# Sheet1.net
KiCad netlist of a schematic drawn in Altium Designer
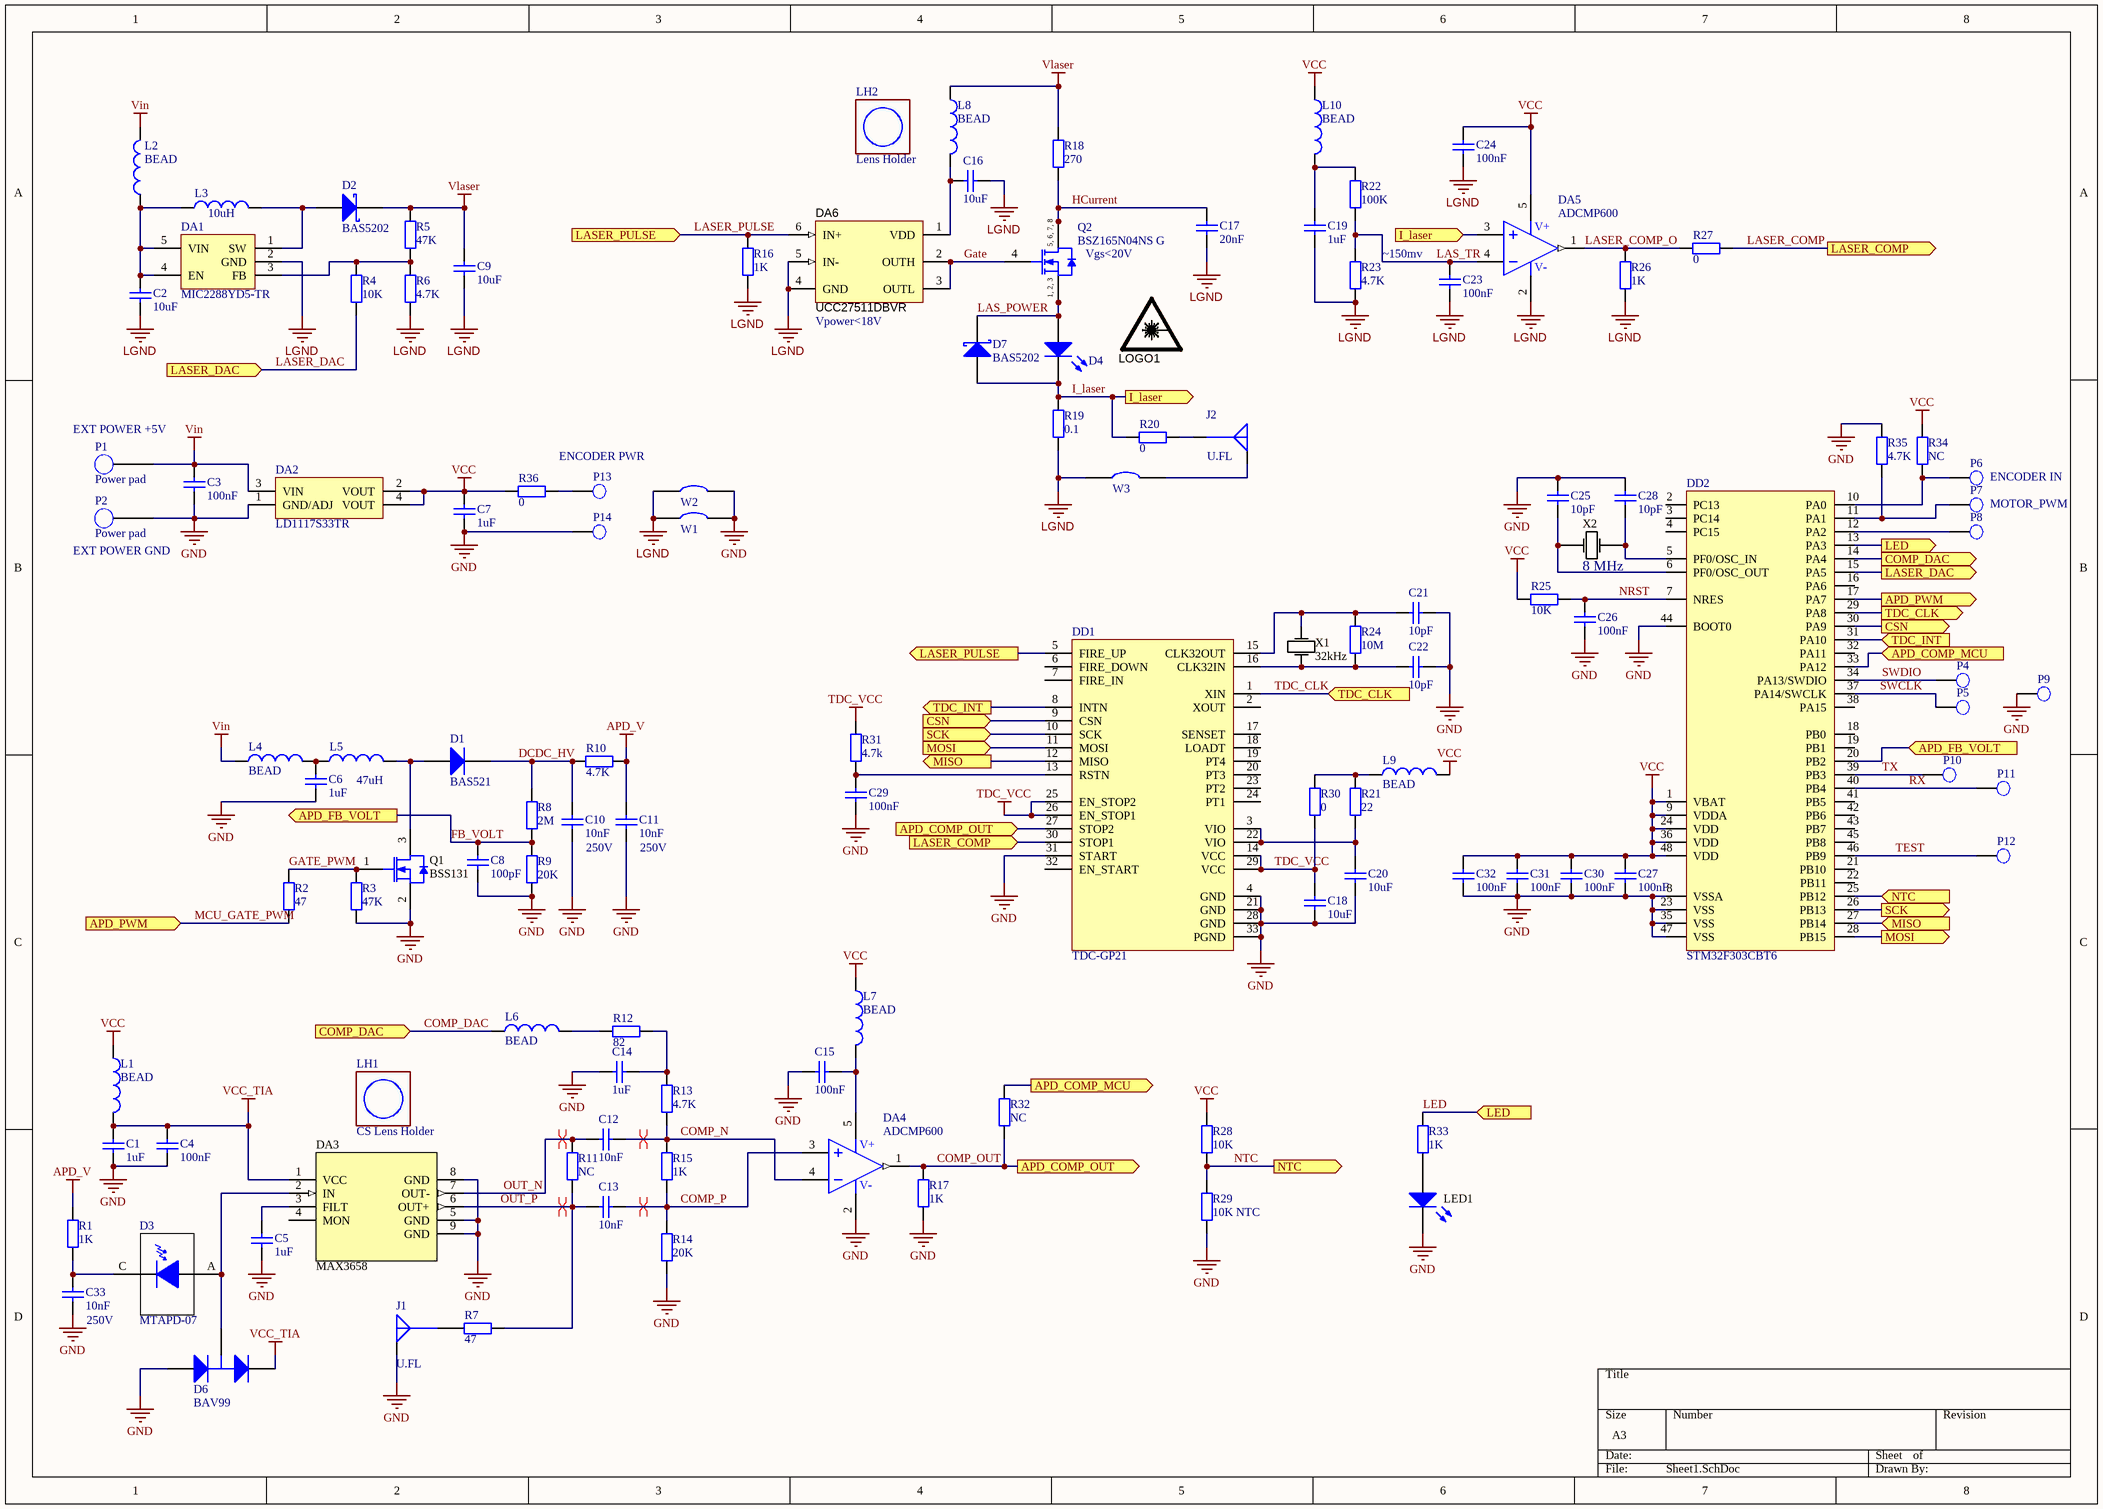
[diagram p0: Sheet1.SchDoc]

(export (version "E")
  (design (tool "Eeschema 10.0.6"))
  (components
    (comp (ref "C1")
      (value "1uF")
      (footprint "CAPC2012X135N")
      (description "Chip capacitor")
      (fields (field (name "VOLTAGE") "25V"))
      (libsource (lib "MyLibSch") (part "CC0805"))
    )
    (comp (ref "C2")
      (value "10uF")
      (footprint "CAPC1608X90N")
      (description "Chip capacitor")
      (fields (field (name "VOLTAGE") "25V"))
      (libsource (lib "MyLibSch") (part "CC0805"))
    )
    (comp (ref "C3")
      (value "100nF")
      (footprint "CAPC1608X90N")
      (description "Chip capacitor")
      (fields (field (name "VOLTAGE") "25V"))
      (libsource (lib "MyLibSch") (part "CC0805"))
    )
    (comp (ref "C4")
      (value "100nF")
      (footprint "CAPC1608X90N")
      (description "Chip capacitor")
      (fields (field (name "VOLTAGE") "25V"))
      (libsource (lib "MyLibSch") (part "CC0805"))
    )
    (comp (ref "C5")
      (value "1uF")
      (footprint "CAPC1608X90N")
      (description "Chip capacitor")
      (fields (field (name "VOLTAGE") "25V"))
      (libsource (lib "MyLibSch") (part "CC0805"))
    )
    (comp (ref "C6")
      (value "1uF")
      (footprint "CAPC2012X135N")
      (description "Chip capacitor")
      (fields (field (name "VOLTAGE") "25V"))
      (libsource (lib "MyLibSch") (part "CC0805"))
    )
    (comp (ref "C7")
      (value "1uF")
      (footprint "CAPC2012X135N")
      (description "Chip capacitor")
      (fields (field (name "VOLTAGE") "25V"))
      (libsource (lib "MyLibSch") (part "CC0805"))
    )
    (comp (ref "C8")
      (value "100pF")
      (footprint "CAPC1608X90N")
      (description "Chip capacitor")
      (fields (field (name "VOLTAGE") "25V"))
      (libsource (lib "MyLibSch") (part "CC0805"))
    )
    (comp (ref "C9")
      (value "10uF")
      (footprint "CAPC1608X90N")
      (description "Chip capacitor")
      (fields (field (name "VOLTAGE") "50V"))
      (libsource (lib "MyLibSch") (part "CC0805"))
    )
    (comp (ref "C10")
      (value "10nF")
      (footprint "CAPC2012X135N")
      (description "Chip capacitor")
      (fields (field (name "VOLTAGE") "250V"))
      (libsource (lib "MyLibSch") (part "CC0805"))
    )
    (comp (ref "C11")
      (value "10nF")
      (footprint "CAPC2012X135N")
      (description "Chip capacitor")
      (fields (field (name "VOLTAGE") "250V"))
      (libsource (lib "MyLibSch") (part "CC0805"))
    )
    (comp (ref "C12")
      (value "10nF")
      (footprint "CAPC1608X90N")
      (description "Chip capacitor")
      (fields (field (name "VOLTAGE") "25V"))
      (libsource (lib "MyLibSch") (part "CC0805"))
    )
    (comp (ref "C13")
      (value "10nF")
      (footprint "CAPC1608X90N")
      (description "Chip capacitor")
      (fields (field (name "VOLTAGE") "25V"))
      (libsource (lib "MyLibSch") (part "CC0805"))
    )
    (comp (ref "C14")
      (value "1uF")
      (footprint "CAPC2012X135N")
      (description "Chip capacitor")
      (fields (field (name "VOLTAGE") "25V"))
      (libsource (lib "MyLibSch") (part "CC0805"))
    )
    (comp (ref "C15")
      (value "100nF")
      (footprint "CAPC1608X90N")
      (description "Chip capacitor")
      (fields (field (name "VOLTAGE") "25V"))
      (libsource (lib "MyLibSch") (part "CC0805"))
    )
    (comp (ref "C16")
      (value "10uF")
      (footprint "CAPC1608X90N")
      (description "Chip capacitor")
      (fields (field (name "VOLTAGE") "25V"))
      (libsource (lib "MyLibSch") (part "CC0805"))
    )
    (comp (ref "C17")
      (value "20nF")
      (footprint "CAPC1608X90N")
      (description "Chip capacitor")
      (fields (field (name "VOLTAGE") "50V"))
      (libsource (lib "MyLibSch") (part "CC0805"))
    )
    (comp (ref "C18")
      (value "10uF")
      (footprint "CAPC1608X90N")
      (description "Chip capacitor")
      (fields (field (name "VOLTAGE") "25V"))
      (libsource (lib "MyLibSch") (part "CC0805"))
    )
    (comp (ref "C19")
      (value "1uF")
      (footprint "CAPC2012X135N")
      (description "Chip capacitor")
      (fields (field (name "VOLTAGE") "25V"))
      (libsource (lib "MyLibSch") (part "CC0805"))
    )
    (comp (ref "C20")
      (value "10uF")
      (footprint "CAPC1608X90N")
      (description "Chip capacitor")
      (fields (field (name "VOLTAGE") "25V"))
      (libsource (lib "MyLibSch") (part "CC0805"))
    )
    (comp (ref "C21")
      (value "10pF")
      (footprint "CAPC1608X90N")
      (description "Chip capacitor")
      (fields (field (name "VOLTAGE") "25V"))
      (libsource (lib "MyLibSch") (part "CC0805"))
    )
    (comp (ref "C22")
      (value "10pF")
      (footprint "CAPC1608X90N")
      (description "Chip capacitor")
      (fields (field (name "VOLTAGE") "25V"))
      (libsource (lib "MyLibSch") (part "CC0805"))
    )
    (comp (ref "C23")
      (value "100nF")
      (footprint "CAPC1608X90N")
      (description "Chip capacitor")
      (fields (field (name "VOLTAGE") "25V"))
      (libsource (lib "MyLibSch") (part "CC0805"))
    )
    (comp (ref "C24")
      (value "100nF")
      (footprint "CAPC1608X90N")
      (description "Chip capacitor")
      (fields (field (name "VOLTAGE") "25V"))
      (libsource (lib "MyLibSch") (part "CC0805"))
    )
    (comp (ref "C25")
      (value "10pF")
      (footprint "CAPC1608X90N")
      (description "Chip capacitor")
      (fields (field (name "VOLTAGE") "25V"))
      (libsource (lib "MyLibSch") (part "CC0805"))
    )
    (comp (ref "C26")
      (value "100nF")
      (footprint "CAPC1608X90N")
      (description "Chip capacitor")
      (fields (field (name "VOLTAGE") "25V"))
      (libsource (lib "MyLibSch") (part "CC0805"))
    )
    (comp (ref "C27")
      (value "100nF")
      (footprint "CAPC1608X90N")
      (description "Chip capacitor")
      (fields (field (name "VOLTAGE") "25V"))
      (libsource (lib "MyLibSch") (part "CC0805"))
    )
    (comp (ref "C28")
      (value "10pF")
      (footprint "CAPC1608X90N")
      (description "Chip capacitor")
      (fields (field (name "VOLTAGE") "25V"))
      (libsource (lib "MyLibSch") (part "CC0805"))
    )
    (comp (ref "C29")
      (value "100nF")
      (footprint "CAPC1608X90N")
      (description "Chip capacitor")
      (fields (field (name "VOLTAGE") "25V"))
      (libsource (lib "MyLibSch") (part "CC0805"))
    )
    (comp (ref "C30")
      (value "100nF")
      (footprint "CAPC1608X90N")
      (description "Chip capacitor")
      (fields (field (name "VOLTAGE") "25V"))
      (libsource (lib "MyLibSch") (part "CC0805"))
    )
    (comp (ref "C31")
      (value "100nF")
      (footprint "CAPC1608X90N")
      (description "Chip capacitor")
      (fields (field (name "VOLTAGE") "25V"))
      (libsource (lib "MyLibSch") (part "CC0805"))
    )
    (comp (ref "C32")
      (value "100nF")
      (footprint "CAPC1608X90N")
      (description "Chip capacitor")
      (fields (field (name "VOLTAGE") "25V"))
      (libsource (lib "MyLibSch") (part "CC0805"))
    )
    (comp (ref "C33")
      (value "10nF")
      (footprint "CAPC2012X135N")
      (description "Chip capacitor")
      (fields (field (name "VOLTAGE") "250V"))
      (libsource (lib "MyLibSch") (part "CC0805"))
    )
    (comp (ref "D1") (value "BAS521") (footprint "SOD523F") (libsource (lib "MyLibSch") (part "DIODE 2 pin")))
    (comp (ref "D2")
      (value "BAS5202")
      (footprint "SOD523F")
      (description "Schottky Diode")
      (fields (field (name "PUBLISHER") "Altium Limited"))
      (libsource (lib "Miscellaneous Devices") (part "D Schottky"))
    )
    (comp (ref "D3")
      (value "MTAPD-07")
      (footprint "LCC3")
      (description "APD photodiode")
      (libsource (lib "lcd_lib") (part "MTAPD-07"))
    )
    (comp (ref "D4")
      (value "Laser SPL PL90_3")
      (footprint "SPL_PL90")
      (description "TO-18 Laser")
      (libsource (lib "lcd_lib") (part "TO-18 Laser"))
    )
    (comp (ref "D6")
      (value "BAV99")
      (footprint "SOT-23")
      (description "Silicon Switching Diode Array for High-Speed Switching")
      (fields (field (name "PUBLISHER") "Altium Limited"))
      (libsource (lib "Infineon Discrete Diode") (part "BAV99"))
    )
    (comp (ref "D7")
      (value "BAS5202")
      (footprint "SOD523F")
      (description "Schottky Diode")
      (fields (field (name "PUBLISHER") "Altium Limited"))
      (libsource (lib "Miscellaneous Devices") (part "D Schottky"))
    )
    (comp (ref "DA1")
      (value "MIC2288YD5-TR")
      (footprint "SOT23-5")
      (description "Step Up")
      (libsource (lib "lcd_lib") (part "MIC2288"))
    )
    (comp (ref "DA2")
      (value "LD1117S33TR")
      (footprint "SOT223")
      (description "LOW DROP FIXED AND ADJUSTABLE  POSITIVE VOLTAGE REGULATORS")
      (libsource (lib "MyLibSch") (part "LD1117S"))
    )
    (comp (ref "DA3")
      (value "MAX3658")
      (footprint "TDFN-8_0.65")
      (description "Transimpedance Amplifier")
      (fields (field (name "PART NUMBER") "AD7278"))
      (libsource (lib "lcd_lib") (part "MAX3658"))
    )
    (comp (ref "DA4")
      (value "ADCMP600")
      (footprint "SOT23-5")
      (description "Fast comparator")
      (libsource (lib "lcd_lib") (part "ADCMP600"))
    )
    (comp (ref "DA5")
      (value "ADCMP600")
      (footprint "SOT23-5")
      (description "Fast comparator")
      (libsource (lib "lcd_lib") (part "ADCMP600"))
    )
    (comp (ref "DA6")
      (value "UCC27511DBVR")
      (footprint "Miscellaneous Devices:SOT23-6_M")
      (description "Single-Channel High-Speed Low-Side Gate Driver (with 4-A Peak Source and 8-A Peak Sink), DBV0006A")
      (fields
        (field (name "ALTERNATE PARTNUMBER") "UCC27511DBVT")
        (field (name "MANUFACTURER") "Texas Instruments")
        (field (name "SYMBOLCREATOR") "a0411947")
        (field (name "PUBLISHER") "Texas Instruments")
      )
      (libsource (lib "TI_Pre_Release") (part "UCC27511DBVR"))
    )
    (comp (ref "DD1")
      (value "TDC-GP21")
      (footprint "QFN32 5x5mm")
      (description "TDC")
      (libsource (lib "lcd_lib") (part "TDC_GP21"))
    )
    (comp (ref "DD2")
      (value "STM32F303CBT6")
      (footprint "LQFP-48_N")
      (description "Microcontroller")
      (libsource (lib "lcd_lib") (part "STM32F3_LQFP48"))
    )
    (comp (ref "J1")
      (value "U.FL")
      (footprint "TE C-1909763")
      (description "U.FL Connector")
      (libsource (lib "RF Connector") (part "RF Connector - SMA"))
    )
    (comp (ref "J2")
      (value "U.FL")
      (footprint "TE C-1909763")
      (description "U.FL Connector")
      (libsource (lib "RF Connector") (part "RF Connector - SMA"))
    )
    (comp (ref "L1")
      (value "BEAD")
      (footprint "INDC1608N")
      (description "Ferrit Bead")
      (libsource (lib "MyLibSch") (part "BEAD"))
    )
    (comp (ref "L2")
      (value "BEAD")
      (footprint "INDC1608N")
      (description "Ferrit Bead")
      (libsource (lib "MyLibSch") (part "BEAD"))
    )
    (comp (ref "L3")
      (value "10uH")
      (footprint "MyLibPcb:V0805HD")
      (description "Inductor")
      (fields (field (name "PUBLISHER") "Altium Limited"))
      (libsource (lib "Miscellaneous Devices") (part "Inductor"))
    )
    (comp (ref "L4")
      (value "BEAD")
      (footprint "INDC1608N")
      (description "Ferrit Bead")
      (libsource (lib "MyLibSch") (part "BEAD"))
    )
    (comp (ref "L5")
      (value "47uH")
      (footprint "INDC3216")
      (description "Inductor")
      (fields (field (name "PUBLISHER") "Altium Limited"))
      (libsource (lib "Miscellaneous Devices") (part "Inductor"))
    )
    (comp (ref "L6")
      (value "BEAD")
      (footprint "INDC1608N")
      (description "Ferrit Bead")
      (libsource (lib "MyLibSch") (part "BEAD"))
    )
    (comp (ref "L7")
      (value "BEAD")
      (footprint "INDC1608N")
      (description "Ferrit Bead")
      (libsource (lib "MyLibSch") (part "BEAD"))
    )
    (comp (ref "L8")
      (value "BEAD")
      (footprint "INDC1608N")
      (description "Ferrit Bead")
      (libsource (lib "MyLibSch") (part "BEAD"))
    )
    (comp (ref "L9")
      (value "BEAD")
      (footprint "INDC1608N")
      (description "Ferrit Bead")
      (libsource (lib "MyLibSch") (part "BEAD"))
    )
    (comp (ref "L10")
      (value "BEAD")
      (footprint "INDC1608N")
      (description "Ferrit Bead")
      (libsource (lib "MyLibSch") (part "BEAD"))
    )
    (comp (ref "LED1")
      (value "LED")
      (footprint "PcbLib3:LED_0603")
      (description "LED_0603")
      (libsource (lib "lcd_lib") (part "LED_0603"))
    )
    (comp (ref "LH1")
      (value "CS Lens Holder")
      (footprint "Lens Holder CS")
      (libsource (lib "lcd_lib") (part "CS Lens Holder"))
    )
    (comp (ref "LH2")
      (value "Lens Holder")
      (footprint "LENS_HOLDER_20MM_ADJ")
      (description "M12 Lens Holder")
      (libsource (lib "lcd_lib") (part "M12 Lens Holder"))
    )
    (comp (ref "LOGO1")
      (value "LASER RADIATION")
      (footprint "LaserWarning_Small")
      (description "Laser Warning Symbol")
      (fields (field (name "SYMBOLCREATOR") "a0412235") (field (name "PUBLISHER") "Texas Instruments"))
      (libsource (lib "Logos") (part "Laser_Warning"))
    )
    (comp (ref "P1")
      (value "Power pad")
      (footprint "Ext_power_pad")
      (description "Pad for wire")
      (libsource (lib "lcd_lib") (part "Power_pad"))
    )
    (comp (ref "P2")
      (value "Power pad")
      (footprint "Ext_power_pad")
      (description "Pad for wire")
      (libsource (lib "lcd_lib") (part "Power_pad"))
    )
    (comp (ref "P4")
      (value "Pad")
      (footprint "PcbLib3:Ext_pad_2")
      (description "Pad for wire")
      (libsource (lib "lcd_lib") (part "Ext Pad"))
    )
    (comp (ref "P5")
      (value "Pad")
      (footprint "PcbLib3:Ext_pad_2")
      (description "Pad for wire")
      (libsource (lib "lcd_lib") (part "Ext Pad"))
    )
    (comp (ref "P6")
      (value "Pad")
      (footprint "PcbLib3:Ext_pad_2")
      (description "Pad for wire")
      (libsource (lib "lcd_lib") (part "Ext Pad"))
    )
    (comp (ref "P7")
      (value "Pad")
      (footprint "PcbLib3:Ext_pad_2")
      (description "Pad for wire")
      (libsource (lib "lcd_lib") (part "Ext Pad"))
    )
    (comp (ref "P8")
      (value "Pad")
      (footprint "PcbLib3:Ext_pad_2")
      (description "Pad for wire")
      (libsource (lib "lcd_lib") (part "Ext Pad"))
    )
    (comp (ref "P9")
      (value "Pad")
      (footprint "PcbLib3:Ext_pad_2")
      (description "Pad for wire")
      (libsource (lib "lcd_lib") (part "Ext Pad"))
    )
    (comp (ref "P10")
      (value "Pad")
      (footprint "PcbLib3:Ext_pad_2")
      (description "Pad for wire")
      (libsource (lib "lcd_lib") (part "Ext Pad"))
    )
    (comp (ref "P11")
      (value "Pad")
      (footprint "PcbLib3:Ext_pad_2")
      (description "Pad for wire")
      (libsource (lib "lcd_lib") (part "Ext Pad"))
    )
    (comp (ref "P12")
      (value "Pad")
      (footprint "PcbLib3:Ext_pad_2")
      (description "Pad for wire")
      (libsource (lib "lcd_lib") (part "Ext Pad"))
    )
    (comp (ref "P13")
      (value "Pad")
      (footprint "PcbLib3:Ext_pad_2")
      (description "Pad for wire")
      (libsource (lib "lcd_lib") (part "Ext Pad"))
    )
    (comp (ref "P14")
      (value "Pad")
      (footprint "PcbLib3:Ext_pad_2")
      (description "Pad for wire")
      (libsource (lib "lcd_lib") (part "Ext Pad"))
    )
    (comp (ref "Q1")
      (value "BSS131")
      (footprint "INF-PG-SOT23_N")
      (fields (field (name "MANUFACTURER") "Infineon"))
      (libsource (lib "altium-import") (part "root_0_BSS131_"))
    )
    (comp (ref "Q2")
      (value "BSZ165N04NS G")
      (footprint "INF-PG-TSDSON-8-1_A_V")
      (fields (field (name "MANUFACTURER") "Infineon"))
      (libsource (lib "BSZ165N04NS G") (part "BSZ165N04NS G"))
    )
    (comp (ref "R1")
      (value "1K")
      (footprint "RESC1608X55N")
      (description "Chip resistor")
      (fields (field (name "TOLERANCE") "5%"))
      (libsource (lib "MyLibSch") (part "RC0805"))
    )
    (comp (ref "R2")
      (value "47")
      (footprint "RESC1608X55N")
      (description "Chip resistor")
      (fields (field (name "TOLERANCE") "5%"))
      (libsource (lib "MyLibSch") (part "RC0805"))
    )
    (comp (ref "R3")
      (value "47K")
      (footprint "RESC1608X55N")
      (description "Chip resistor")
      (fields (field (name "TOLERANCE") "5%"))
      (libsource (lib "") (part "RC0805_3"))
    )
    (comp (ref "R4")
      (value "10K")
      (footprint "RESC1608X55N")
      (description "Chip resistor")
      (fields (field (name "TOLERANCE") "5%"))
      (libsource (lib "MyLibSch") (part "RC0805"))
    )
    (comp (ref "R5")
      (value "47K")
      (footprint "RESC1608X55N")
      (description "Chip resistor")
      (fields (field (name "TOLERANCE") "5%"))
      (libsource (lib "MyLibSch") (part "RC0805"))
    )
    (comp (ref "R6")
      (value "4.7K")
      (footprint "RESC1608X55N")
      (description "Chip resistor")
      (fields (field (name "TOLERANCE") "5%"))
      (libsource (lib "MyLibSch") (part "RC0805"))
    )
    (comp (ref "R7")
      (value "47")
      (footprint "RESC1608X55N")
      (description "Chip resistor")
      (fields (field (name "TOLERANCE") "5%"))
      (libsource (lib "MyLibSch") (part "RC0805"))
    )
    (comp (ref "R8")
      (value "2M")
      (footprint "RESC2012X70N")
      (description "Chip resistor")
      (fields (field (name "TOLERANCE") "5%"))
      (libsource (lib "MyLibSch") (part "RC0805"))
    )
    (comp (ref "R9")
      (value "20K")
      (footprint "RESC1608X55N")
      (description "Chip resistor")
      (fields (field (name "TOLERANCE") "5%"))
      (libsource (lib "") (part "RC0805_3"))
    )
    (comp (ref "R10")
      (value "4.7K")
      (footprint "RESC1608X55N")
      (description "Chip resistor")
      (fields (field (name "TOLERANCE") "5%"))
      (libsource (lib "") (part "RC0805_1"))
    )
    (comp (ref "R11")
      (value "NC")
      (footprint "RESC1608X55N")
      (description "Chip resistor")
      (fields (field (name "TOLERANCE") "5%"))
      (libsource (lib "MyLibSch") (part "RC0805"))
    )
    (comp (ref "R12")
      (value "82")
      (footprint "RESC1608X55N")
      (description "Chip resistor")
      (fields (field (name "TOLERANCE") "5%"))
      (libsource (lib "") (part "RC0805_1"))
    )
    (comp (ref "R13")
      (value "4.7K")
      (footprint "RESC1608X55N")
      (description "Chip resistor")
      (fields (field (name "TOLERANCE") "5%"))
      (libsource (lib "MyLibSch") (part "RC0805"))
    )
    (comp (ref "R14")
      (value "20K")
      (footprint "RESC2012X70N")
      (description "Chip resistor")
      (fields (field (name "TOLERANCE") "5%"))
      (libsource (lib "MyLibSch") (part "RC0805"))
    )
    (comp (ref "R15")
      (value "1K")
      (footprint "RESC1608X55N")
      (description "Chip resistor")
      (fields (field (name "TOLERANCE") "5%"))
      (libsource (lib "MyLibSch") (part "RC0805"))
    )
    (comp (ref "R16")
      (value "1K")
      (footprint "RESC1608X55N")
      (description "Chip resistor")
      (fields (field (name "TOLERANCE") "5%"))
      (libsource (lib "MyLibSch") (part "RC0805"))
    )
    (comp (ref "R17")
      (value "1K")
      (footprint "RESC1608X55N")
      (description "Chip resistor")
      (fields (field (name "TOLERANCE") "5%"))
      (libsource (lib "MyLibSch") (part "RC0805"))
    )
    (comp (ref "R18")
      (value "270")
      (footprint "RESC1608X55N")
      (description "Chip resistor")
      (fields (field (name "TOLERANCE") "5%"))
      (libsource (lib "MyLibSch") (part "RC0805"))
    )
    (comp (ref "R19")
      (value "0.1")
      (footprint "RESC2012X70N")
      (description "Chip resistor")
      (fields (field (name "TOLERANCE") "5%"))
      (libsource (lib "MyLibSch") (part "RC0805"))
    )
    (comp (ref "R20")
      (value "0")
      (footprint "RESC1608X55N")
      (description "Chip resistor")
      (fields (field (name "TOLERANCE") "5%"))
      (libsource (lib "") (part "RC0805_1"))
    )
    (comp (ref "R21")
      (value "22")
      (footprint "RESC1608X55N")
      (description "Chip resistor")
      (fields (field (name "TOLERANCE") "5%"))
      (libsource (lib "") (part "RC0805_3"))
    )
    (comp (ref "R22")
      (value "100K")
      (footprint "RESC1608X55N")
      (description "Chip resistor")
      (fields (field (name "TOLERANCE") "5%"))
      (libsource (lib "") (part "RC0805_3"))
    )
    (comp (ref "R23")
      (value "4.7K")
      (footprint "RESC1608X55N")
      (description "Chip resistor")
      (fields (field (name "TOLERANCE") "5%"))
      (libsource (lib "") (part "RC0805_3"))
    )
    (comp (ref "R24")
      (value "10M")
      (footprint "RESC1608X55N")
      (description "Chip resistor")
      (fields (field (name "TOLERANCE") "5%"))
      (libsource (lib "MyLibSch") (part "RC0805"))
    )
    (comp (ref "R25")
      (value "10K")
      (footprint "RESC1608X55N")
      (description "Chip resistor")
      (fields (field (name "TOLERANCE") "5%"))
      (libsource (lib "") (part "RC0805_2"))
    )
    (comp (ref "R26")
      (value "1K")
      (footprint "RESC1608X55N")
      (description "Chip resistor")
      (fields (field (name "TOLERANCE") "5%"))
      (libsource (lib "MyLibSch") (part "RC0805"))
    )
    (comp (ref "R27")
      (value "0")
      (footprint "RESC1608X55N")
      (description "Chip resistor")
      (fields (field (name "TOLERANCE") "5%"))
      (libsource (lib "") (part "RC0805_2"))
    )
    (comp (ref "R28")
      (value "10K")
      (footprint "RESC1608X55N")
      (description "Chip resistor")
      (fields (field (name "TOLERANCE") "5%"))
      (libsource (lib "") (part "RC0805_3"))
    )
    (comp (ref "R29")
      (value "10K NTC")
      (footprint "RESC1608X55N")
      (description "Chip resistor")
      (fields (field (name "TOLERANCE") "5%"))
      (libsource (lib "MyLibSch") (part "RC0805"))
    )
    (comp (ref "R30")
      (value "0")
      (footprint "RESC1608X55N")
      (description "Chip resistor")
      (fields (field (name "TOLERANCE") "5%"))
      (libsource (lib "") (part "RC0805_3"))
    )
    (comp (ref "R31")
      (value "4.7k")
      (footprint "RESC1608X55N")
      (description "Chip resistor")
      (fields (field (name "TOLERANCE") "5%"))
      (libsource (lib "") (part "RC0805_3"))
    )
    (comp (ref "R32")
      (value "NC")
      (footprint "RESC1608X55N")
      (description "Chip resistor")
      (fields (field (name "TOLERANCE") "5%"))
      (libsource (lib "") (part "RC0805_3"))
    )
    (comp (ref "R33")
      (value "1K")
      (footprint "RESC1608X55N")
      (description "Chip resistor")
      (fields (field (name "TOLERANCE") "5%"))
      (libsource (lib "MyLibSch") (part "RC0805"))
    )
    (comp (ref "R34")
      (value "NC")
      (footprint "RESC1608X55N")
      (description "Chip resistor")
      (fields (field (name "TOLERANCE") "5%"))
      (libsource (lib "") (part "RC0805_3"))
    )
    (comp (ref "R35")
      (value "4.7K")
      (footprint "RESC1608X55N")
      (description "Chip resistor")
      (fields (field (name "TOLERANCE") "5%"))
      (libsource (lib "") (part "RC0805_3"))
    )
    (comp (ref "R36")
      (value "0")
      (footprint "RESC1608X55N")
      (description "Chip resistor")
      (fields (field (name "TOLERANCE") "5%"))
      (libsource (lib "") (part "RC0805_2"))
    )
    (comp (ref "W1")
      (value "NET connector")
      (footprint "Net connector")
      (libsource (lib "lcd_lib") (part "NET connector"))
    )
    (comp (ref "W2")
      (value "NET connector")
      (footprint "Net connector")
      (libsource (lib "lcd_lib") (part "NET connector"))
    )
    (comp (ref "W3")
      (value "NET connector")
      (footprint "Net connector2")
      (libsource (lib "lcd_lib") (part "NET connector"))
    )
    (comp (ref "X1")
      (value "32kHz")
      (footprint "QUARTZ_32K")
      (description "Quartz")
      (libsource (lib "lcd_lib") (part "Quartz_32k"))
    )
    (comp (ref "X2")
      (value "8 MHz")
      (footprint "SX-6 QUARTZ")
      (description "Quartz_SX-6 (SMD06035C4)")
      (fields (field (name "Comment") "Quartz"))
      (libsource (lib "lcd_lib") (part "Quartz_SX-6"))
    )
  )
  (nets
    (net (code "1") (name "/APD_COMP_MCU") (class "Default")
      (node (ref "DD2") (pin "33") (pinfunction "PA12_33") (pintype "passive"))
      (node (ref "R32") (pin "1") (pinfunction "1_1") (pintype "passive"))
    )
    (net (code "2") (name "/COMP_DAC") (class "Default")
      (node (ref "DD2") (pin "14") (pinfunction "PA4_14") (pintype "passive"))
      (node (ref "L6") (pin "1") (pinfunction "1_1") (pintype "passive"))
    )
    (net (code "3") (name "/COMP_N") (class "Default")
      (node (ref "C12") (pin "1") (pinfunction "1_1") (pintype "passive"))
      (node (ref "DA4") (pin "4") (pinfunction "IN-_4") (pintype "passive"))
      (node (ref "R13") (pin "1") (pinfunction "1_1") (pintype "passive"))
      (node (ref "R15") (pin "2") (pinfunction "2_2") (pintype "passive"))
    )
    (net (code "4") (name "/COMP_OUT") (class "Default")
      (node (ref "DA4") (pin "1") (pinfunction "OUT_1") (pintype "output"))
      (node (ref "DD1") (pin "27") (pinfunction "STOP2_27") (pintype "passive"))
      (node (ref "R17") (pin "2") (pinfunction "2_2") (pintype "passive"))
      (node (ref "R32") (pin "2") (pinfunction "2_2") (pintype "passive"))
    )
    (net (code "5") (name "/COMP_P") (class "Default")
      (node (ref "C13") (pin "1") (pinfunction "1_1") (pintype "passive"))
      (node (ref "DA4") (pin "3") (pinfunction "IN+_3") (pintype "passive"))
      (node (ref "R14") (pin "2") (pinfunction "2_2") (pintype "passive"))
      (node (ref "R15") (pin "1") (pinfunction "1_1") (pintype "passive"))
    )
    (net (code "6") (name "/CSN") (class "Default")
      (node (ref "DD1") (pin "9") (pinfunction "CSN_9") (pintype "passive"))
      (node (ref "DD2") (pin "30") (pinfunction "PA9_30") (pintype "passive"))
    )
    (net (code "7") (name "/DCDC_HV") (class "Default")
      (node (ref "C10") (pin "2") (pinfunction "2_2") (pintype "passive"))
      (node (ref "D1") (pin "K") (pinfunction "K_K") (pintype "passive"))
      (node (ref "R10") (pin "2") (pinfunction "2_2") (pintype "passive"))
      (node (ref "R8") (pin "2") (pinfunction "2_2") (pintype "passive"))
    )
    (net (code "8") (name "/FB_VOLT") (class "Default")
      (node (ref "C8") (pin "1") (pinfunction "1_1") (pintype "passive"))
      (node (ref "DD2") (pin "20") (pinfunction "PB2_20") (pintype "passive"))
      (node (ref "R8") (pin "1") (pinfunction "1_1") (pintype "passive"))
      (node (ref "R9") (pin "1") (pinfunction "1_1") (pintype "passive"))
    )
    (net (code "9") (name "/GATE_PWM") (class "Default")
      (node (ref "Q1") (pin "1") (pinfunction "GATE_1") (pintype "passive"))
      (node (ref "R2") (pin "2") (pinfunction "2_2") (pintype "passive"))
      (node (ref "R3") (pin "1") (pinfunction "1_1") (pintype "passive"))
    )
    (net (code "10") (name "/Gate") (class "Default")
      (node (ref "DA6") (pin "2") (pinfunction "OUTH_2") (pintype "power_in"))
      (node (ref "DA6") (pin "3") (pinfunction "OUTL_3") (pintype "power_in"))
      (node (ref "Q2") (pin "4") (pinfunction "GATE_4") (pintype "passive"))
    )
    (net (code "11") (name "/HCurrent") (class "Default")
      (node (ref "C17") (pin "2") (pinfunction "2_2") (pintype "passive"))
      (node (ref "Q2") (pin "5") (pinfunction "DRAIN_5") (pintype "passive"))
      (node (ref "Q2") (pin "6") (pinfunction "DRAIN_6") (pintype "passive"))
      (node (ref "Q2") (pin "7") (pinfunction "DRAIN_7") (pintype "passive"))
      (node (ref "Q2") (pin "8") (pinfunction "DRAIN_8") (pintype "passive"))
      (node (ref "R18") (pin "1") (pinfunction "1_1") (pintype "passive"))
    )
    (net (code "12") (name "/I_laser") (class "Default")
      (node (ref "D4") (pin "K") (pinfunction "K_K") (pintype "passive"))
      (node (ref "D7") (pin "A") (pinfunction "A_A") (pintype "passive"))
      (node (ref "DA5") (pin "3") (pinfunction "IN+_3") (pintype "passive"))
      (node (ref "R19") (pin "2") (pinfunction "2_2") (pintype "passive"))
      (node (ref "R20") (pin "2") (pinfunction "2_2") (pintype "passive"))
    )
    (net (code "13") (name "/LASER_COMP") (class "Default")
      (node (ref "DD1") (pin "30") (pinfunction "STOP1_30") (pintype "passive"))
      (node (ref "R27") (pin "2") (pinfunction "2_2") (pintype "passive"))
    )
    (net (code "14") (name "/LASER_COMP_O") (class "Default")
      (node (ref "DA5") (pin "1") (pinfunction "OUT_1") (pintype "output"))
      (node (ref "R26") (pin "2") (pinfunction "2_2") (pintype "passive"))
      (node (ref "R27") (pin "1") (pinfunction "1_1") (pintype "passive"))
    )
    (net (code "15") (name "/LASER_DAC") (class "Default")
      (node (ref "DD2") (pin "15") (pinfunction "PA5_15") (pintype "passive"))
      (node (ref "R4") (pin "1") (pinfunction "1_1") (pintype "passive"))
    )
    (net (code "16") (name "/LASER_PULSE") (class "Default")
      (node (ref "DA6") (pin "6") (pinfunction "IN+_6") (pintype "input"))
      (node (ref "DD1") (pin "5") (pinfunction "FIRE_UP_5") (pintype "passive"))
      (node (ref "R16") (pin "2") (pinfunction "2_2") (pintype "passive"))
    )
    (net (code "17") (name "/LAS_POWER") (class "Default")
      (node (ref "D4") (pin "A") (pinfunction "A_A") (pintype "passive"))
      (node (ref "D7") (pin "K") (pinfunction "K_K") (pintype "passive"))
      (node (ref "Q2") (pin "1") (pinfunction "SOURCE_1") (pintype "passive"))
      (node (ref "Q2") (pin "2") (pinfunction "SOURCE_2") (pintype "passive"))
      (node (ref "Q2") (pin "3") (pinfunction "SOURCE_3") (pintype "passive"))
    )
    (net (code "18") (name "/LAS_TR") (class "Default")
      (node (ref "C23") (pin "2") (pinfunction "2_2") (pintype "passive"))
      (node (ref "DA5") (pin "4") (pinfunction "IN-_4") (pintype "passive"))
      (node (ref "R22") (pin "2") (pinfunction "2_2") (pintype "passive"))
      (node (ref "R23") (pin "1") (pinfunction "1_1") (pintype "passive"))
    )
    (net (code "19") (name "/LED") (class "Default")
      (node (ref "DD2") (pin "13") (pinfunction "PA3_13") (pintype "passive"))
      (node (ref "R33") (pin "2") (pinfunction "2_2") (pintype "passive"))
    )
    (net (code "20") (name "/MCU_GATE_PWM") (class "Default")
      (node (ref "DD2") (pin "17") (pinfunction "PA7_17") (pintype "passive"))
      (node (ref "R2") (pin "1") (pinfunction "1_1") (pintype "passive"))
    )
    (net (code "21") (name "/MISO") (class "Default")
      (node (ref "DD1") (pin "12") (pinfunction "MISO_12") (pintype "passive"))
      (node (ref "DD2") (pin "27") (pinfunction "PB14_27") (pintype "passive"))
    )
    (net (code "22") (name "/MOSI") (class "Default")
      (node (ref "DD1") (pin "11") (pinfunction "MOSI_11") (pintype "passive"))
      (node (ref "DD2") (pin "28") (pinfunction "PB15_28") (pintype "passive"))
    )
    (net (code "23") (name "/NRST") (class "Default")
      (node (ref "C26") (pin "2") (pinfunction "2_2") (pintype "passive"))
      (node (ref "DD2") (pin "7") (pinfunction "NRES_7") (pintype "passive"))
      (node (ref "R25") (pin "2") (pinfunction "2_2") (pintype "passive"))
    )
    (net (code "24") (name "/NTC") (class "Default")
      (node (ref "DD2") (pin "25") (pinfunction "PB12_25") (pintype "passive"))
      (node (ref "R28") (pin "2") (pinfunction "2_2") (pintype "passive"))
      (node (ref "R29") (pin "2") (pinfunction "2_2") (pintype "passive"))
    )
    (net (code "25") (name "/OUT_N") (class "Default")
      (node (ref "C12") (pin "2") (pinfunction "2_2") (pintype "passive"))
      (node (ref "DA3") (pin "7") (pinfunction "OUT-_7") (pintype "output"))
      (node (ref "R11") (pin "2") (pinfunction "2_2") (pintype "passive"))
    )
    (net (code "26") (name "/OUT_P") (class "Default")
      (node (ref "C13") (pin "2") (pinfunction "2_2") (pintype "passive"))
      (node (ref "DA3") (pin "6") (pinfunction "OUT+_6") (pintype "output"))
      (node (ref "R11") (pin "1") (pinfunction "1_1") (pintype "passive"))
      (node (ref "R7") (pin "2") (pinfunction "2_2") (pintype "passive"))
    )
    (net (code "27") (name "/RX") (class "Default")
      (node (ref "DD2") (pin "40") (pinfunction "PB4_40") (pintype "passive"))
      (node (ref "P11") (pin "1") (pinfunction "Pad_1") (pintype "passive"))
    )
    (net (code "28") (name "/SCK") (class "Default")
      (node (ref "DD1") (pin "10") (pinfunction "SCK_10") (pintype "passive"))
      (node (ref "DD2") (pin "26") (pinfunction "PB13_26") (pintype "passive"))
    )
    (net (code "29") (name "/SWCLK") (class "Default")
      (node (ref "DD2") (pin "37") (pinfunction "PA14/SWCLK_37") (pintype "passive"))
      (node (ref "P5") (pin "1") (pinfunction "Pad_1") (pintype "passive"))
    )
    (net (code "30") (name "/SWDIO") (class "Default")
      (node (ref "DD2") (pin "34") (pinfunction "PA13/SWDIO_34") (pintype "passive"))
      (node (ref "P4") (pin "1") (pinfunction "Pad_1") (pintype "passive"))
    )
    (net (code "31") (name "/TDC_CLK") (class "Default")
      (node (ref "DD1") (pin "1") (pinfunction "XIN_1") (pintype "passive"))
      (node (ref "DD2") (pin "29") (pinfunction "PA8_29") (pintype "passive"))
    )
    (net (code "32") (name "/TDC_INT") (class "Default")
      (node (ref "DD1") (pin "8") (pinfunction "INTN_8") (pintype "passive"))
      (node (ref "DD2") (pin "31") (pinfunction "PA10_31") (pintype "passive"))
    )
    (net (code "33") (name "/TEST") (class "Default")
      (node (ref "DD2") (pin "46") (pinfunction "PB9_46") (pintype "passive"))
      (node (ref "P12") (pin "1") (pinfunction "Pad_1") (pintype "passive"))
    )
    (net (code "34") (name "/TX") (class "Default")
      (node (ref "DD2") (pin "39") (pinfunction "PB3_39") (pintype "passive"))
      (node (ref "P10") (pin "1") (pinfunction "Pad_1") (pintype "passive"))
    )
    (net (code "35") (name "APD_V") (class "Default")
      (node (ref "C11") (pin "2") (pinfunction "2_2") (pintype "passive"))
      (node (ref "R1") (pin "2") (pinfunction "2_2") (pintype "passive"))
      (node (ref "R10") (pin "1") (pinfunction "1_1") (pintype "passive"))
    )
    (net (code "36") (name "GND") (class "Default")
      (node (ref "C1") (pin "1") (pinfunction "1_1") (pintype "passive"))
      (node (ref "C10") (pin "1") (pinfunction "1_1") (pintype "passive"))
      (node (ref "C11") (pin "1") (pinfunction "1_1") (pintype "passive"))
      (node (ref "C14") (pin "2") (pinfunction "2_2") (pintype "passive"))
      (node (ref "C15") (pin "2") (pinfunction "2_2") (pintype "passive"))
      (node (ref "C18") (pin "1") (pinfunction "1_1") (pintype "passive"))
      (node (ref "C20") (pin "1") (pinfunction "1_1") (pintype "passive"))
      (node (ref "C21") (pin "1") (pinfunction "1_1") (pintype "passive"))
      (node (ref "C22") (pin "1") (pinfunction "1_1") (pintype "passive"))
      (node (ref "C25") (pin "2") (pinfunction "2_2") (pintype "passive"))
      (node (ref "C26") (pin "1") (pinfunction "1_1") (pintype "passive"))
      (node (ref "C27") (pin "1") (pinfunction "1_1") (pintype "passive"))
      (node (ref "C28") (pin "2") (pinfunction "2_2") (pintype "passive"))
      (node (ref "C29") (pin "1") (pinfunction "1_1") (pintype "passive"))
      (node (ref "C3") (pin "1") (pinfunction "1_1") (pintype "passive"))
      (node (ref "C30") (pin "1") (pinfunction "1_1") (pintype "passive"))
      (node (ref "C31") (pin "1") (pinfunction "1_1") (pintype "passive"))
      (node (ref "C32") (pin "1") (pinfunction "1_1") (pintype "passive"))
      (node (ref "C33") (pin "1") (pinfunction "1_1") (pintype "passive"))
      (node (ref "C4") (pin "1") (pinfunction "1_1") (pintype "passive"))
      (node (ref "C5") (pin "1") (pinfunction "1_1") (pintype "passive"))
      (node (ref "C6") (pin "2") (pinfunction "2_2") (pintype "passive"))
      (node (ref "C7") (pin "1") (pinfunction "1_1") (pintype "passive"))
      (node (ref "C8") (pin "2") (pinfunction "2_2") (pintype "passive"))
      (node (ref "D6") (pin "1") (pinfunction "A_1") (pintype "passive"))
      (node (ref "DA2") (pin "1") (pinfunction "GND/ADJ_1") (pintype "power_in"))
      (node (ref "DA3") (pin "5") (pinfunction "GND_5") (pintype "power_in"))
      (node (ref "DA3") (pin "8") (pinfunction "GND_8") (pintype "power_in"))
      (node (ref "DA3") (pin "9") (pinfunction "GND_9") (pintype "power_in"))
      (node (ref "DA4") (pin "2") (pinfunction "V-_2") (pintype "power_in"))
      (node (ref "DD1") (pin "21") (pinfunction "GND_21") (pintype "passive"))
      (node (ref "DD1") (pin "28") (pinfunction "GND_28") (pintype "passive"))
      (node (ref "DD1") (pin "31") (pinfunction "START_31") (pintype "passive"))
      (node (ref "DD1") (pin "33") (pinfunction "PGND_33") (pintype "passive"))
      (node (ref "DD1") (pin "4") (pinfunction "GND_4") (pintype "passive"))
      (node (ref "DD2") (pin "23") (pinfunction "VSS_23") (pintype "passive"))
      (node (ref "DD2") (pin "35") (pinfunction "VSS_35") (pintype "passive"))
      (node (ref "DD2") (pin "44") (pinfunction "BOOT0_44") (pintype "passive"))
      (node (ref "DD2") (pin "47") (pinfunction "VSS_47") (pintype "passive"))
      (node (ref "DD2") (pin "8") (pinfunction "VSSA_8") (pintype "passive"))
      (node (ref "J1") (pin "G") (pinfunction "G_G") (pintype "passive"))
      (node (ref "LED1") (pin "2") (pinfunction "K_2") (pintype "passive"))
      (node (ref "P14") (pin "1") (pinfunction "Pad_1") (pintype "passive"))
      (node (ref "P2") (pin "1") (pinfunction "47_1") (pintype "passive"))
      (node (ref "P9") (pin "1") (pinfunction "Pad_1") (pintype "passive"))
      (node (ref "Q1") (pin "2") (pinfunction "SOURCE_2") (pintype "passive"))
      (node (ref "R14") (pin "1") (pinfunction "1_1") (pintype "passive"))
      (node (ref "R17") (pin "1") (pinfunction "1_1") (pintype "passive"))
      (node (ref "R29") (pin "1") (pinfunction "1_1") (pintype "passive"))
      (node (ref "R3") (pin "2") (pinfunction "2_2") (pintype "passive"))
      (node (ref "R35") (pin "1") (pinfunction "1_1") (pintype "passive"))
      (node (ref "R9") (pin "2") (pinfunction "2_2") (pintype "passive"))
      (node (ref "W1") (pin "2") (pinfunction "2_2") (pintype "passive"))
      (node (ref "W2") (pin "2") (pinfunction "2_2") (pintype "passive"))
    )
    (net (code "37") (name "LGND") (class "Default")
      (node (ref "C16") (pin "1") (pinfunction "1_1") (pintype "passive"))
      (node (ref "C17") (pin "1") (pinfunction "1_1") (pintype "passive"))
      (node (ref "C19") (pin "1") (pinfunction "1_1") (pintype "passive"))
      (node (ref "C2") (pin "1") (pinfunction "1_1") (pintype "passive"))
      (node (ref "C23") (pin "1") (pinfunction "1_1") (pintype "passive"))
      (node (ref "C24") (pin "1") (pinfunction "1_1") (pintype "passive"))
      (node (ref "C9") (pin "1") (pinfunction "1_1") (pintype "passive"))
      (node (ref "DA1") (pin "2") (pinfunction "GND_2") (pintype "power_in"))
      (node (ref "DA5") (pin "2") (pinfunction "V-_2") (pintype "power_in"))
      (node (ref "DA6") (pin "4") (pinfunction "GND_4") (pintype "power_in"))
      (node (ref "DA6") (pin "5") (pinfunction "IN-_5") (pintype "input"))
      (node (ref "R16") (pin "1") (pinfunction "1_1") (pintype "passive"))
      (node (ref "R19") (pin "1") (pinfunction "1_1") (pintype "passive"))
      (node (ref "R23") (pin "2") (pinfunction "2_2") (pintype "passive"))
      (node (ref "R26") (pin "1") (pinfunction "1_1") (pintype "passive"))
      (node (ref "R6") (pin "1") (pinfunction "1_1") (pintype "passive"))
      (node (ref "W1") (pin "1") (pinfunction "1_1") (pintype "passive"))
      (node (ref "W2") (pin "1") (pinfunction "1_1") (pintype "passive"))
      (node (ref "W3") (pin "1") (pinfunction "1_1") (pintype "passive"))
    )
    (net (code "38") (name "Net-(C6-Pad1)") (class "Default")
      (node (ref "C6") (pin "1") (pinfunction "1_1") (pintype "passive"))
      (node (ref "L4") (pin "2") (pinfunction "2_2") (pintype "passive"))
      (node (ref "L5") (pin "1") (pinfunction "1_1") (pintype "passive"))
    )
    (net (code "39") (name "Net-(C14-Pad1)") (class "Default")
      (node (ref "C14") (pin "1") (pinfunction "1_1") (pintype "passive"))
      (node (ref "R12") (pin "1") (pinfunction "1_1") (pintype "passive"))
      (node (ref "R13") (pin "2") (pinfunction "2_2") (pintype "passive"))
    )
    (net (code "40") (name "Net-(C19-Pad2)") (class "Default")
      (node (ref "C19") (pin "2") (pinfunction "2_2") (pintype "passive"))
      (node (ref "L10") (pin "2") (pinfunction "2_2") (pintype "passive"))
      (node (ref "R22") (pin "1") (pinfunction "1_1") (pintype "passive"))
    )
    (net (code "41") (name "Net-(C20-Pad2)") (class "Default")
      (node (ref "C20") (pin "2") (pinfunction "2_2") (pintype "passive"))
      (node (ref "DD1") (pin "22") (pinfunction "VIO_22") (pintype "passive"))
      (node (ref "DD1") (pin "3") (pinfunction "VIO_3") (pintype "passive"))
      (node (ref "R21") (pin "2") (pinfunction "2_2") (pintype "passive"))
    )
    (net (code "42") (name "Net-(C33-Pad2)") (class "Default")
      (node (ref "C33") (pin "2") (pinfunction "2_2") (pintype "passive"))
      (node (ref "D3") (pin "C") (pinfunction "C_C") (pintype "passive"))
      (node (ref "R1") (pin "1") (pinfunction "1_1") (pintype "passive"))
    )
    (net (code "43") (name "Net-(D6-C)") (class "Default")
      (node (ref "D3") (pin "A") (pinfunction "A_A") (pintype "passive"))
      (node (ref "D6") (pin "3") (pinfunction "C_3") (pintype "passive"))
      (node (ref "DA3") (pin "2") (pinfunction "IN_2") (pintype "input"))
    )
    (net (code "44") (name "Net-(DA1-EN)") (class "Default")
      (node (ref "C2") (pin "2") (pinfunction "2_2") (pintype "passive"))
      (node (ref "DA1") (pin "4") (pinfunction "EN_4") (pintype "power_in"))
      (node (ref "DA1") (pin "5") (pinfunction "VIN_5") (pintype "passive"))
      (node (ref "L2") (pin "1") (pinfunction "1_1") (pintype "passive"))
      (node (ref "L3") (pin "1") (pinfunction "1_1") (pintype "passive"))
    )
    (net (code "45") (name "Net-(DA1-FB)") (class "Default")
      (node (ref "DA1") (pin "3") (pinfunction "FB_3") (pintype "power_in"))
      (node (ref "R4") (pin "2") (pinfunction "2_2") (pintype "passive"))
      (node (ref "R5") (pin "1") (pinfunction "1_1") (pintype "passive"))
      (node (ref "R6") (pin "2") (pinfunction "2_2") (pintype "passive"))
    )
    (net (code "46") (name "Net-(DA1-SW)") (class "Default")
      (node (ref "D2") (pin "A") (pinfunction "A_A") (pintype "passive"))
      (node (ref "DA1") (pin "1") (pinfunction "SW_1") (pintype "open_collector"))
      (node (ref "L3") (pin "2") (pinfunction "2_2") (pintype "passive"))
    )
    (net (code "47") (name "Net-(DA3-FILT)") (class "Default")
      (node (ref "C5") (pin "2") (pinfunction "2_2") (pintype "passive"))
      (node (ref "DA3") (pin "3") (pinfunction "FILT_3") (pintype "passive"))
    )
    (net (code "48") (name "Net-(DA4-V+)") (class "Default")
      (node (ref "C15") (pin "1") (pinfunction "1_1") (pintype "passive"))
      (node (ref "DA4") (pin "5") (pinfunction "V+_5") (pintype "power_in"))
      (node (ref "L7") (pin "2") (pinfunction "2_2") (pintype "passive"))
    )
    (net (code "49") (name "Net-(DA6-VDD)") (class "Default")
      (node (ref "C16") (pin "2") (pinfunction "2_2") (pintype "passive"))
      (node (ref "DA6") (pin "1") (pinfunction "VDD_1") (pintype "power_in"))
      (node (ref "L8") (pin "2") (pinfunction "2_2") (pintype "passive"))
    )
    (net (code "50") (name "Net-(DD1-CLK32IN)") (class "Default")
      (node (ref "C22") (pin "2") (pinfunction "2_2") (pintype "passive"))
      (node (ref "DD1") (pin "16") (pinfunction "CLK32IN_16") (pintype "passive"))
      (node (ref "R24") (pin "1") (pinfunction "1_1") (pintype "passive"))
      (node (ref "X1") (pin "2") (pinfunction "2_2") (pintype "passive"))
    )
    (net (code "51") (name "Net-(DD1-CLK32OUT)") (class "Default")
      (node (ref "C21") (pin "2") (pinfunction "2_2") (pintype "passive"))
      (node (ref "DD1") (pin "15") (pinfunction "CLK32OUT_15") (pintype "passive"))
      (node (ref "R24") (pin "2") (pinfunction "2_2") (pintype "passive"))
      (node (ref "X1") (pin "1") (pinfunction "1_1") (pintype "passive"))
    )
    (net (code "52") (name "Net-(DD1-RSTN)") (class "Default")
      (node (ref "C29") (pin "2") (pinfunction "2_2") (pintype "passive"))
      (node (ref "DD1") (pin "13") (pinfunction "RSTN_13") (pintype "passive"))
      (node (ref "R31") (pin "2") (pinfunction "2_2") (pintype "passive"))
    )
    (net (code "53") (name "Net-(DD2-PA0)") (class "Default")
      (node (ref "DD2") (pin "10") (pinfunction "PA0_10") (pintype "passive"))
      (node (ref "P6") (pin "1") (pinfunction "Pad_1") (pintype "passive"))
      (node (ref "R34") (pin "2") (pinfunction "2_2") (pintype "passive"))
    )
    (net (code "54") (name "Net-(DD2-PA1)") (class "Default")
      (node (ref "DD2") (pin "11") (pinfunction "PA1_11") (pintype "passive"))
      (node (ref "P7") (pin "1") (pinfunction "Pad_1") (pintype "passive"))
      (node (ref "R35") (pin "2") (pinfunction "2_2") (pintype "passive"))
    )
    (net (code "55") (name "Net-(DD2-PA2)") (class "Default")
      (node (ref "DD2") (pin "12") (pinfunction "PA2_12") (pintype "passive"))
      (node (ref "P8") (pin "1") (pinfunction "Pad_1") (pintype "passive"))
    )
    (net (code "56") (name "Net-(DD2-PF0{slash}OSC_IN)") (class "Default")
      (node (ref "C28") (pin "1") (pinfunction "1_1") (pintype "passive"))
      (node (ref "DD2") (pin "5") (pinfunction "PF0/OSC_IN_5") (pintype "passive"))
      (node (ref "X2") (pin "3") (pinfunction "3_3") (pintype "passive"))
    )
    (net (code "57") (name "Net-(DD2-PF0{slash}OSC_OUT)") (class "Default")
      (node (ref "C25") (pin "1") (pinfunction "1_1") (pintype "passive"))
      (node (ref "DD2") (pin "6") (pinfunction "PF0/OSC_OUT_6") (pintype "passive"))
      (node (ref "X2") (pin "1") (pinfunction "1_1") (pintype "passive"))
    )
    (net (code "58") (name "Net-(J1-PadS)") (class "Default")
      (node (ref "J1") (pin "S") (pinfunction "S_S") (pintype "passive"))
      (node (ref "R7") (pin "1") (pinfunction "1_1") (pintype "passive"))
    )
    (net (code "59") (name "Net-(J2-PadG)") (class "Default")
      (node (ref "J2") (pin "G") (pinfunction "G_G") (pintype "passive"))
      (node (ref "W3") (pin "2") (pinfunction "2_2") (pintype "passive"))
    )
    (net (code "60") (name "Net-(J2-PadS)") (class "Default")
      (node (ref "J2") (pin "S") (pinfunction "S_S") (pintype "passive"))
      (node (ref "R20") (pin "1") (pinfunction "1_1") (pintype "passive"))
    )
    (net (code "61") (name "Net-(L6-Pad2)") (class "Default")
      (node (ref "L6") (pin "2") (pinfunction "2_2") (pintype "passive"))
      (node (ref "R12") (pin "2") (pinfunction "2_2") (pintype "passive"))
    )
    (net (code "62") (name "Net-(L9-Pad1)") (class "Default")
      (node (ref "L9") (pin "1") (pinfunction "1_1") (pintype "passive"))
      (node (ref "R21") (pin "1") (pinfunction "1_1") (pintype "passive"))
      (node (ref "R30") (pin "1") (pinfunction "1_1") (pintype "passive"))
    )
    (net (code "63") (name "Net-(LED1-A)") (class "Default")
      (node (ref "LED1") (pin "1") (pinfunction "A_1") (pintype "passive"))
      (node (ref "R33") (pin "1") (pinfunction "1_1") (pintype "passive"))
    )
    (net (code "64") (name "Net-(P13-Pad)") (class "Default")
      (node (ref "P13") (pin "1") (pinfunction "Pad_1") (pintype "passive"))
      (node (ref "R36") (pin "2") (pinfunction "2_2") (pintype "passive"))
    )
    (net (code "65") (name "Net-(Q1-DRAIN)") (class "Default")
      (node (ref "D1") (pin "A") (pinfunction "A_A") (pintype "passive"))
      (node (ref "L5") (pin "2") (pinfunction "2_2") (pintype "passive"))
      (node (ref "Q1") (pin "3") (pinfunction "DRAIN_3") (pintype "passive"))
    )
    (net (code "66") (name "TDC_VCC") (class "Default")
      (node (ref "C18") (pin "2") (pinfunction "2_2") (pintype "passive"))
      (node (ref "DD1") (pin "14") (pinfunction "VCC_14") (pintype "passive"))
      (node (ref "DD1") (pin "25") (pinfunction "EN_STOP2_25") (pintype "passive"))
      (node (ref "DD1") (pin "26") (pinfunction "EN_STOP1_26") (pintype "passive"))
      (node (ref "DD1") (pin "29") (pinfunction "VCC_29") (pintype "passive"))
      (node (ref "R30") (pin "2") (pinfunction "2_2") (pintype "passive"))
      (node (ref "R31") (pin "1") (pinfunction "1_1") (pintype "passive"))
    )
    (net (code "67") (name "VCC") (class "Default")
      (node (ref "C24") (pin "2") (pinfunction "2_2") (pintype "passive"))
      (node (ref "C27") (pin "2") (pinfunction "2_2") (pintype "passive"))
      (node (ref "C30") (pin "2") (pinfunction "2_2") (pintype "passive"))
      (node (ref "C31") (pin "2") (pinfunction "2_2") (pintype "passive"))
      (node (ref "C32") (pin "2") (pinfunction "2_2") (pintype "passive"))
      (node (ref "C7") (pin "2") (pinfunction "2_2") (pintype "passive"))
      (node (ref "DA2") (pin "2") (pinfunction "VOUT_2") (pintype "power_in"))
      (node (ref "DA2") (pin "4") (pinfunction "VOUT_4") (pintype "power_in"))
      (node (ref "DA5") (pin "5") (pinfunction "V+_5") (pintype "power_in"))
      (node (ref "DD2") (pin "1") (pinfunction "VBAT_1") (pintype "passive"))
      (node (ref "DD2") (pin "24") (pinfunction "VDD_24") (pintype "passive"))
      (node (ref "DD2") (pin "36") (pinfunction "VDD_36") (pintype "passive"))
      (node (ref "DD2") (pin "48") (pinfunction "VDD_48") (pintype "passive"))
      (node (ref "DD2") (pin "9") (pinfunction "VDDA_9") (pintype "passive"))
      (node (ref "L1") (pin "1") (pinfunction "1_1") (pintype "passive"))
      (node (ref "L10") (pin "1") (pinfunction "1_1") (pintype "passive"))
      (node (ref "L7") (pin "1") (pinfunction "1_1") (pintype "passive"))
      (node (ref "L9") (pin "2") (pinfunction "2_2") (pintype "passive"))
      (node (ref "R25") (pin "1") (pinfunction "1_1") (pintype "passive"))
      (node (ref "R28") (pin "1") (pinfunction "1_1") (pintype "passive"))
      (node (ref "R34") (pin "1") (pinfunction "1_1") (pintype "passive"))
      (node (ref "R36") (pin "1") (pinfunction "1_1") (pintype "passive"))
    )
    (net (code "68") (name "VCC_TIA") (class "Default")
      (node (ref "C1") (pin "2") (pinfunction "2_2") (pintype "passive"))
      (node (ref "C4") (pin "2") (pinfunction "2_2") (pintype "passive"))
      (node (ref "D6") (pin "2") (pinfunction "K_2") (pintype "passive"))
      (node (ref "DA3") (pin "1") (pinfunction "VCC_1") (pintype "power_in"))
      (node (ref "L1") (pin "2") (pinfunction "2_2") (pintype "passive"))
    )
    (net (code "69") (name "Vin") (class "Default")
      (node (ref "C3") (pin "2") (pinfunction "2_2") (pintype "passive"))
      (node (ref "DA2") (pin "3") (pinfunction "VIN_3") (pintype "power_in"))
      (node (ref "L2") (pin "2") (pinfunction "2_2") (pintype "passive"))
      (node (ref "L4") (pin "1") (pinfunction "1_1") (pintype "passive"))
      (node (ref "P1") (pin "1") (pinfunction "47_1") (pintype "passive"))
    )
    (net (code "70") (name "Vlaser") (class "Default")
      (node (ref "C9") (pin "2") (pinfunction "2_2") (pintype "passive"))
      (node (ref "D2") (pin "K") (pinfunction "K_K") (pintype "passive"))
      (node (ref "L8") (pin "1") (pinfunction "1_1") (pintype "passive"))
      (node (ref "R18") (pin "2") (pinfunction "2_2") (pintype "passive"))
      (node (ref "R5") (pin "2") (pinfunction "2_2") (pintype "passive"))
    )
    (net (code "71") (name "unconnected-(DA3-MON-Pad4)") (class "Default")
      (node (ref "DA3") (pin "4") (pinfunction "MON_4") (pintype "passive"))
    )
    (net (code "72") (name "unconnected-(DD1-EN_START-Pad32)") (class "Default")
      (node (ref "DD1") (pin "32") (pinfunction "EN_START_32") (pintype "passive"))
    )
    (net (code "73") (name "unconnected-(DD1-FIRE_DOWN-Pad6)") (class "Default")
      (node (ref "DD1") (pin "6") (pinfunction "FIRE_DOWN_6") (pintype "passive"))
    )
    (net (code "74") (name "unconnected-(DD1-FIRE_IN-Pad7)") (class "Default")
      (node (ref "DD1") (pin "7") (pinfunction "FIRE_IN_7") (pintype "passive"))
    )
    (net (code "75") (name "unconnected-(DD1-LOADT-Pad18)") (class "Default")
      (node (ref "DD1") (pin "18") (pinfunction "LOADT_18") (pintype "passive"))
    )
    (net (code "76") (name "unconnected-(DD1-PT1-Pad24)") (class "Default")
      (node (ref "DD1") (pin "24") (pinfunction "PT1_24") (pintype "passive"))
    )
    (net (code "77") (name "unconnected-(DD1-PT2-Pad23)") (class "Default")
      (node (ref "DD1") (pin "23") (pinfunction "PT2_23") (pintype "passive"))
    )
    (net (code "78") (name "unconnected-(DD1-PT3-Pad20)") (class "Default")
      (node (ref "DD1") (pin "20") (pinfunction "PT3_20") (pintype "passive"))
    )
    (net (code "79") (name "unconnected-(DD1-PT4-Pad19)") (class "Default")
      (node (ref "DD1") (pin "19") (pinfunction "PT4_19") (pintype "passive"))
    )
    (net (code "80") (name "unconnected-(DD1-SENSET-Pad17)") (class "Default")
      (node (ref "DD1") (pin "17") (pinfunction "SENSET_17") (pintype "passive"))
    )
    (net (code "81") (name "unconnected-(DD1-XOUT-Pad2)") (class "Default")
      (node (ref "DD1") (pin "2") (pinfunction "XOUT_2") (pintype "passive"))
    )
    (net (code "82") (name "unconnected-(DD2-PA6-Pad16)") (class "Default")
      (node (ref "DD2") (pin "16") (pinfunction "PA6_16") (pintype "passive"))
    )
    (net (code "83") (name "unconnected-(DD2-PA11-Pad32)") (class "Default")
      (node (ref "DD2") (pin "32") (pinfunction "PA11_32") (pintype "passive"))
    )
    (net (code "84") (name "unconnected-(DD2-PA15-Pad38)") (class "Default")
      (node (ref "DD2") (pin "38") (pinfunction "PA15_38") (pintype "passive"))
    )
    (net (code "85") (name "unconnected-(DD2-PB0-Pad18)") (class "Default")
      (node (ref "DD2") (pin "18") (pinfunction "PB0_18") (pintype "passive"))
    )
    (net (code "86") (name "unconnected-(DD2-PB1-Pad19)") (class "Default")
      (node (ref "DD2") (pin "19") (pinfunction "PB1_19") (pintype "passive"))
    )
    (net (code "87") (name "unconnected-(DD2-PB5-Pad41)") (class "Default")
      (node (ref "DD2") (pin "41") (pinfunction "PB5_41") (pintype "passive"))
    )
    (net (code "88") (name "unconnected-(DD2-PB6-Pad42)") (class "Default")
      (node (ref "DD2") (pin "42") (pinfunction "PB6_42") (pintype "passive"))
    )
    (net (code "89") (name "unconnected-(DD2-PB7-Pad43)") (class "Default")
      (node (ref "DD2") (pin "43") (pinfunction "PB7_43") (pintype "passive"))
    )
    (net (code "90") (name "unconnected-(DD2-PB8-Pad45)") (class "Default")
      (node (ref "DD2") (pin "45") (pinfunction "PB8_45") (pintype "passive"))
    )
    (net (code "91") (name "unconnected-(DD2-PB10-Pad21)") (class "Default")
      (node (ref "DD2") (pin "21") (pinfunction "PB10_21") (pintype "passive"))
    )
    (net (code "92") (name "unconnected-(DD2-PB11-Pad22)") (class "Default")
      (node (ref "DD2") (pin "22") (pinfunction "PB11_22") (pintype "passive"))
    )
    (net (code "93") (name "unconnected-(DD2-PC13-Pad2)") (class "Default")
      (node (ref "DD2") (pin "2") (pinfunction "PC13_2") (pintype "passive"))
    )
    (net (code "94") (name "unconnected-(DD2-PC14-Pad3)") (class "Default")
      (node (ref "DD2") (pin "3") (pinfunction "PC14_3") (pintype "passive"))
    )
    (net (code "95") (name "unconnected-(DD2-PC15-Pad4)") (class "Default")
      (node (ref "DD2") (pin "4") (pinfunction "PC15_4") (pintype "passive"))
    )
  )
)
